# DW1000.net
KiCad netlist of a schematic drawn in Altium Designer
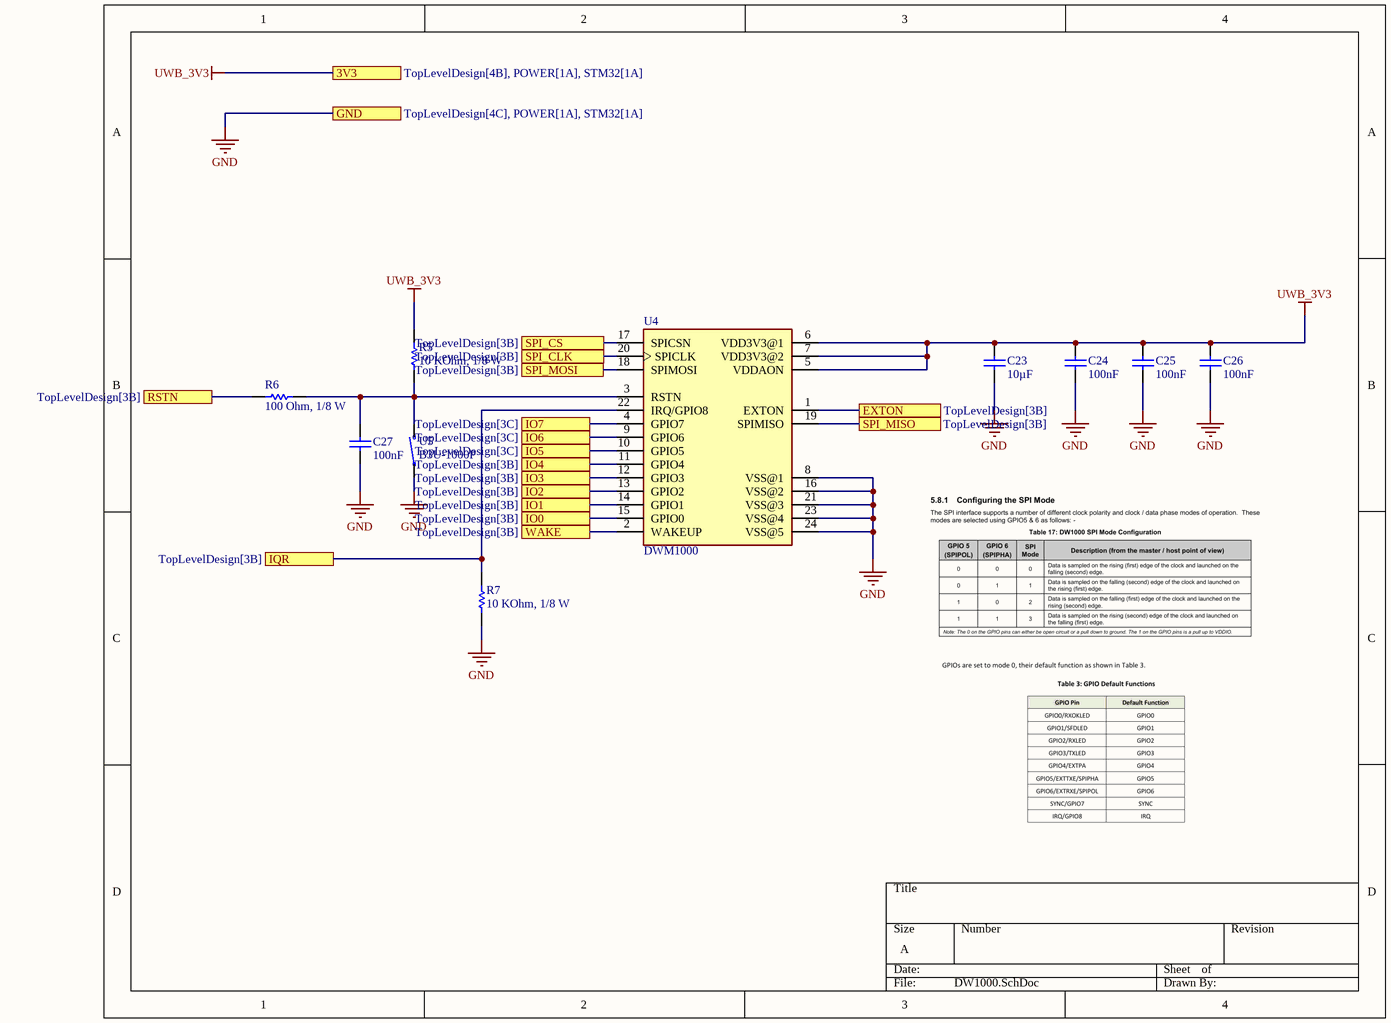
[diagram p0: DW1000.SchDoc]

(export (version "E")
  (design (tool "Eeschema 10.0.6"))
  (components
    (comp (ref "C23")
      (value "10µF")
      (footprint "CAP_0805")
      (description "CAP, size 0805, 10 uF, 25 VDC")
      (fields
        (field (name "TOLERANCE") "10%")
        (field (name "Comment") "0108051061025")
        (field (name "SOURCE") "Capacitor_0805_10_percent.SchLib")
      )
      (libsource (lib "Tin Tran") (part "0108056841050"))
    )
    (comp (ref "C24")
      (value "100nF")
      (footprint "CAP_0603")
      (description "CAP, size 0603, 100 nF, 50 VDC")
      (fields
        (field (name "TOLERANCE") "10%")
        (field (name "Comment") "0106031041050")
        (field (name "SOURCE") "Capacitor_0603_10_percent.SchLib")
      )
      (libsource (lib "Tin Tran") (part "010603475106.3"))
    )
    (comp (ref "C25")
      (value "100nF")
      (footprint "CAP_0603")
      (description "CAP, size 0603, 100 nF, 50 VDC")
      (fields
        (field (name "TOLERANCE") "10%")
        (field (name "Comment") "0106031041050")
        (field (name "SOURCE") "Capacitor_0603_10_percent.SchLib")
      )
      (libsource (lib "Tin Tran") (part "010603475106.3"))
    )
    (comp (ref "C26")
      (value "100nF")
      (footprint "CAP_0603")
      (description "CAP, size 0603, 100 nF, 50 VDC")
      (fields
        (field (name "TOLERANCE") "10%")
        (field (name "Comment") "0106031041050")
        (field (name "SOURCE") "Capacitor_0603_10_percent.SchLib")
      )
      (libsource (lib "Tin Tran") (part "010603475106.3"))
    )
    (comp (ref "C27")
      (value "100nF")
      (footprint "CAP_0603")
      (description "CAP, size 0603, 100 nF, 50 VDC")
      (fields
        (field (name "TOLERANCE") "10%")
        (field (name "Comment") "0106031041050")
        (field (name "SOURCE") "Capacitor_0603_10_percent.SchLib")
      )
      (libsource (lib "Tin Tran") (part "010603475106.3"))
    )
    (comp (ref "R5")
      (value "10 KOhm, 1/8 W")
      (footprint "RESISTOR_0805")
      (description "RES, size 0805, 10 KOhm, 1/8 W")
      (fields (field (name "Comment") "0008051035"))
      (libsource (lib "Tin Tran") (part "0008052035_1"))
    )
    (comp (ref "R6")
      (value "100 Ohm, 1/8 W")
      (footprint "RESISTOR_0805")
      (description "RES, size 0805, 100 Ohm, 1/8 W")
      (fields (field (name "Comment") "0008051011"))
      (libsource (lib "Tin Tran") (part "0008052035_1"))
    )
    (comp (ref "R7")
      (value "10 KOhm, 1/8 W")
      (footprint "RESISTOR_0805")
      (description "RES, size 0805, 10 KOhm, 1/8 W")
      (fields (field (name "Comment") "0008051035"))
      (libsource (lib "Tin Tran") (part "0008052035_1"))
    )
    (comp (ref "U4")
      (value "DWM1000")
      (footprint "XCVR_DWM1000")
      (description "802.15.4 IR-UWB Transceiver Module 3.5GHz ~ 6.5GHz Integrated, Chip Surface Mount")
      (fields (field (name "MF") "Decawave Limited"))
      (libsource (lib "Tin Tran") (part "DWM1000"))
    )
    (comp (ref "U5")
      (value "B3U-1000P")
      (footprint "SODFL4025X160N")
      (description "Switch Tactile N.O. SPST Round Button Gull Wing 0.05A 12VDC 1.5N SMD T/R")
      (fields (field (name "MP") "B3U1000P") (field (name "MF") "Omron"))
      (libsource (lib "Tin Tran") (part "B3U-1000P"))
    )
  )
  (nets
    (net (code "1") (name "/EXTON") (class "Default")
      (node (ref "U4") (pin "1") (pinfunction "EXTON_1") (pintype "passive"))
    )
    (net (code "2") (name "/IO0") (class "Default")
      (node (ref "U4") (pin "15") (pinfunction "GPIO0_15") (pintype "passive"))
    )
    (net (code "3") (name "/IO1") (class "Default")
      (node (ref "U4") (pin "14") (pinfunction "GPIO1_14") (pintype "passive"))
    )
    (net (code "4") (name "/IO2") (class "Default")
      (node (ref "U4") (pin "13") (pinfunction "GPIO2_13") (pintype "passive"))
    )
    (net (code "5") (name "/IO3") (class "Default")
      (node (ref "U4") (pin "12") (pinfunction "GPIO3_12") (pintype "passive"))
    )
    (net (code "6") (name "/IO4") (class "Default")
      (node (ref "U4") (pin "11") (pinfunction "GPIO4_11") (pintype "passive"))
    )
    (net (code "7") (name "/IO5") (class "Default")
      (node (ref "U4") (pin "10") (pinfunction "GPIO5_10") (pintype "passive"))
    )
    (net (code "8") (name "/IO6") (class "Default")
      (node (ref "U4") (pin "9") (pinfunction "GPIO6_9") (pintype "passive"))
    )
    (net (code "9") (name "/IO7") (class "Default")
      (node (ref "U4") (pin "4") (pinfunction "GPIO7_4") (pintype "passive"))
    )
    (net (code "10") (name "/IQR") (class "Default")
      (node (ref "R7") (pin "2") (pinfunction "2_2") (pintype "passive"))
      (node (ref "U4") (pin "22") (pinfunction "IRQ/GPIO8_22") (pintype "passive"))
    )
    (net (code "11") (name "/RSTN") (class "Default")
      (node (ref "R6") (pin "1") (pinfunction "1_1") (pintype "passive"))
    )
    (net (code "12") (name "/SPI_CLK") (class "Default")
      (node (ref "U4") (pin "20") (pinfunction "SPICLK_20") (pintype "passive"))
    )
    (net (code "13") (name "/SPI_CS") (class "Default")
      (node (ref "U4") (pin "17") (pinfunction "SPICSN_17") (pintype "passive"))
    )
    (net (code "14") (name "/SPI_MISO") (class "Default")
      (node (ref "U4") (pin "19") (pinfunction "SPIMISO_19") (pintype "passive"))
    )
    (net (code "15") (name "/SPI_MOSI") (class "Default")
      (node (ref "U4") (pin "18") (pinfunction "SPIMOSI_18") (pintype "passive"))
    )
    (net (code "16") (name "/WAKE") (class "Default")
      (node (ref "U4") (pin "2") (pinfunction "WAKEUP_2") (pintype "passive"))
    )
    (net (code "17") (name "GND") (class "Default")
      (node (ref "C23") (pin "1") (pinfunction "1_1") (pintype "passive"))
      (node (ref "C24") (pin "1") (pinfunction "1_1") (pintype "passive"))
      (node (ref "C25") (pin "1") (pinfunction "1_1") (pintype "passive"))
      (node (ref "C26") (pin "1") (pinfunction "1_1") (pintype "passive"))
      (node (ref "C27") (pin "1") (pinfunction "1_1") (pintype "passive"))
      (node (ref "R7") (pin "1") (pinfunction "1_1") (pintype "passive"))
      (node (ref "U4") (pin "16") (pinfunction "VSS@2_16") (pintype "passive"))
      (node (ref "U4") (pin "21") (pinfunction "VSS@3_21") (pintype "passive"))
      (node (ref "U4") (pin "23") (pinfunction "VSS@4_23") (pintype "passive"))
      (node (ref "U4") (pin "24") (pinfunction "VSS@5_24") (pintype "passive"))
      (node (ref "U4") (pin "8") (pinfunction "VSS@1_8") (pintype "passive"))
      (node (ref "U5") (pin "1") (pinfunction "1_1") (pintype "passive"))
    )
    (net (code "18") (name "Net-(U4-RSTN)") (class "Default")
      (node (ref "C27") (pin "2") (pinfunction "2_2") (pintype "passive"))
      (node (ref "R5") (pin "1") (pinfunction "1_1") (pintype "passive"))
      (node (ref "R6") (pin "2") (pinfunction "2_2") (pintype "passive"))
      (node (ref "U4") (pin "3") (pinfunction "RSTN_3") (pintype "passive"))
      (node (ref "U5") (pin "2") (pinfunction "2_2") (pintype "passive"))
    )
    (net (code "19") (name "UWB_3V3") (class "Default")
      (node (ref "C23") (pin "2") (pinfunction "2_2") (pintype "passive"))
      (node (ref "C24") (pin "2") (pinfunction "2_2") (pintype "passive"))
      (node (ref "C25") (pin "2") (pinfunction "2_2") (pintype "passive"))
      (node (ref "C26") (pin "2") (pinfunction "2_2") (pintype "passive"))
      (node (ref "R5") (pin "2") (pinfunction "2_2") (pintype "passive"))
      (node (ref "U4") (pin "5") (pinfunction "VDDAON_5") (pintype "passive"))
      (node (ref "U4") (pin "6") (pinfunction "VDD3V3@1_6") (pintype "passive"))
      (node (ref "U4") (pin "7") (pinfunction "VDD3V3@2_7") (pintype "passive"))
    )
  )
)
